# RevA.net
KiCad netlist of a schematic drawn in EAGLE
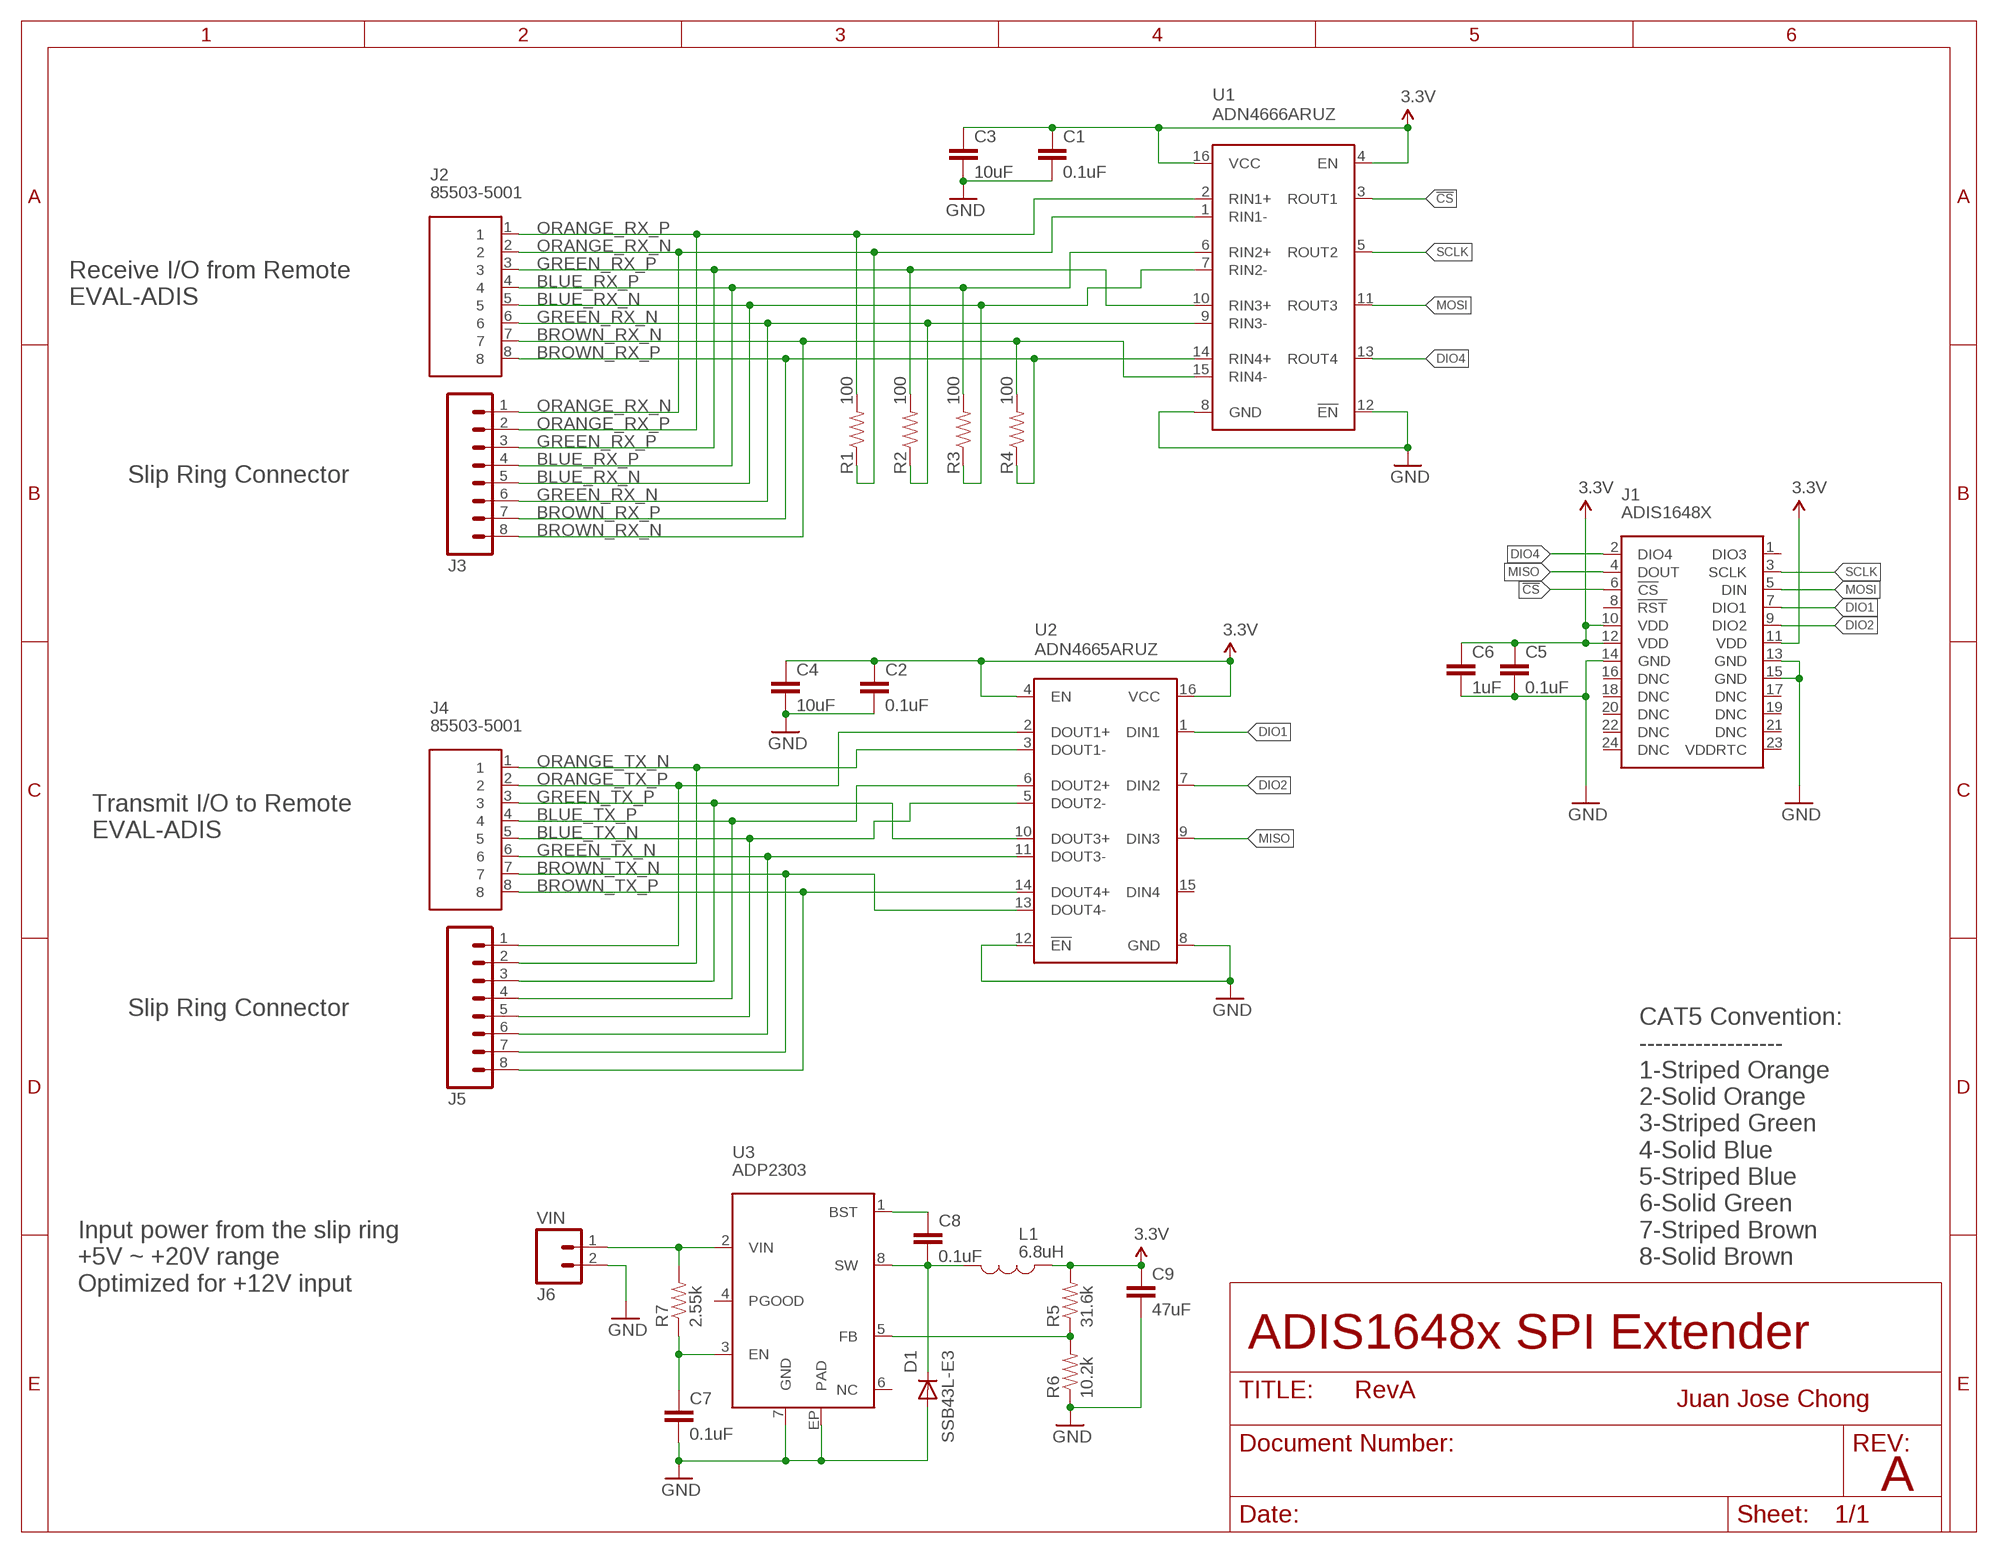
[diagram p0: schematic, sheet 1]

(export (version "E")
  (design (tool "Eeschema 10.0.6"))
  (components
    (comp (ref "C1")
      (value "0.1uF")
      (footprint "eagle-import:0603-CAP")
      (fields (field (name "PARTNO") "CL10B104KB8NNNC"))
      (libsource (lib "eagle-import") (part "CAP0603-CAP"))
    )
    (comp (ref "C2")
      (value "0.1uF")
      (footprint "eagle-import:0603-CAP")
      (fields (field (name "PARTNO") "CL10B104KB8NNNC"))
      (libsource (lib "eagle-import") (part "CAP0603-CAP"))
    )
    (comp (ref "C3")
      (value "10uF")
      (footprint "eagle-import:1206")
      (fields (field (name "PARTNO") "F931C106MAA"))
      (libsource (lib "eagle-import") (part "CAP1206"))
    )
    (comp (ref "C4")
      (value "10uF")
      (footprint "eagle-import:1206")
      (fields (field (name "PARTNO") "F931C106MAA"))
      (libsource (lib "eagle-import") (part "CAP1206"))
    )
    (comp (ref "C5")
      (value "0.1uF")
      (footprint "eagle-import:0603-CAP")
      (fields (field (name "PARTNO") "CL10B104KB8NNNC"))
      (libsource (lib "eagle-import") (part "CAP0603-CAP"))
    )
    (comp (ref "C6")
      (value "1uF")
      (footprint "eagle-import:0603-CAP")
      (fields (field (name "PARTNO") "GRM188R61C105KA93D"))
      (libsource (lib "eagle-import") (part "CAP0603-CAP"))
    )
    (comp (ref "C7")
      (value "0.1uF")
      (footprint "eagle-import:0603-CAP")
      (fields (field (name "PARTNO") "CL10B104KB8NNNC"))
      (libsource (lib "eagle-import") (part "CAP0603-CAP"))
    )
    (comp (ref "C8")
      (value "0.1uF")
      (footprint "eagle-import:0603-CAP")
      (fields (field (name "PARTNO") "CL10B104KB8NNNC"))
      (libsource (lib "eagle-import") (part "CAP0603-CAP"))
    )
    (comp (ref "C9")
      (value "47uF")
      (footprint "eagle-import:1206")
      (fields (field (name "PARTNO") "TLJA476M010R0600"))
      (libsource (lib "eagle-import") (part "CAP1206"))
    )
    (comp (ref "D1")
      (value "SSB43L-E3")
      (footprint "eagle-import:DO214AA")
      (fields (field (name "PARTNO") "SSB43L-E3/52T"))
      (libsource (lib "eagle-import") (part "DIODE-DO214AA"))
    )
    (comp (ref "J1")
      (value "ADIS1648X")
      (footprint "eagle-import:ADIS1648X")
      (libsource (lib "eagle-import") (part "ADIS1648X"))
    )
    (comp (ref "J2")
      (value "85503-5001")
      (footprint "eagle-import:85503-5001")
      (fields (field (name "PARTNO") "855035001"))
      (libsource (lib "eagle-import") (part "85503-5001"))
    )
    (comp (ref "J3")
      (value "M08LOCK")
      (footprint "eagle-import:1X08_LOCK")
      (libsource (lib "eagle-import") (part "M08LOCK"))
    )
    (comp (ref "J4")
      (value "85503-5001")
      (footprint "eagle-import:85503-5001")
      (fields (field (name "PARTNO") "855035001"))
      (libsource (lib "eagle-import") (part "85503-5001"))
    )
    (comp (ref "J5")
      (value "M08LOCK")
      (footprint "eagle-import:1X08_LOCK")
      (libsource (lib "eagle-import") (part "M08LOCK"))
    )
    (comp (ref "J6")
      (value "VIN")
      (footprint "eagle-import:SCREWTERMINAL-3.5MM-2")
      (libsource (lib "eagle-import") (part "M023.5MM"))
    )
    (comp (ref "L1")
      (value "6.8uH")
      (footprint "eagle-import:VLF10040")
      (fields (field (name "PARTNO") "VLF10040T-6R8N4R5"))
      (libsource (lib "eagle-import") (part "INDUCTOR"))
    )
    (comp (ref "R1")
      (value "100")
      (footprint "eagle-import:0603-RES")
      (fields (field (name "PARTNO") "ERJ-3EKF1000V"))
      (libsource (lib "eagle-import") (part "RESISTOR0603-RES"))
    )
    (comp (ref "R2")
      (value "100")
      (footprint "eagle-import:0603-RES")
      (fields (field (name "PARTNO") "ERJ-3EKF1000V"))
      (libsource (lib "eagle-import") (part "RESISTOR0603-RES"))
    )
    (comp (ref "R3")
      (value "100")
      (footprint "eagle-import:0603-RES")
      (fields (field (name "PARTNO") "ERJ-3EKF1000V"))
      (libsource (lib "eagle-import") (part "RESISTOR0603-RES"))
    )
    (comp (ref "R4")
      (value "100")
      (footprint "eagle-import:0603-RES")
      (fields (field (name "PARTNO") "ERJ-3EKF1000V"))
      (libsource (lib "eagle-import") (part "RESISTOR0603-RES"))
    )
    (comp (ref "R5")
      (value "31.6k")
      (footprint "eagle-import:0603-RES")
      (fields (field (name "PARTNO") "ERJ-3EKF3162V"))
      (libsource (lib "eagle-import") (part "RESISTOR0603-RES"))
    )
    (comp (ref "R6")
      (value "10.2k")
      (footprint "eagle-import:0603-RES")
      (fields (field (name "PARTNO") "ERJ-3EKF1022V"))
      (libsource (lib "eagle-import") (part "RESISTOR0603-RES"))
    )
    (comp (ref "R7")
      (value "2.55k")
      (footprint "eagle-import:0603-RES")
      (libsource (lib "eagle-import") (part "RESISTOR0603-RES"))
    )
    (comp (ref "U1")
      (value "ADN4666ARUZ")
      (footprint "eagle-import:TSSOP-16")
      (libsource (lib "eagle-import") (part "ADN4666ARUZ"))
    )
    (comp (ref "U2")
      (value "ADN4665ARUZ")
      (footprint "eagle-import:TSSOP-16")
      (libsource (lib "eagle-import") (part "ADN4665ARUZ"))
    )
    (comp (ref "U3")
      (value "ADP2303")
      (footprint "eagle-import:SOIC-8-PAD")
      (fields (field (name "PARTNO") "ADP2303ARDZ"))
      (libsource (lib "eagle-import") (part "ADP2303"))
    )
  )
  (nets
    (net (code "1") (name "/BLUE_RX_N") (class "Default")
      (node (ref "J2") (pin "5") (pinfunction "5_5") (pintype "bidirectional"))
      (node (ref "J3") (pin "5") (pinfunction "5_5") (pintype "passive"))
      (node (ref "R3") (pin "1") (pinfunction "1_1") (pintype "passive"))
      (node (ref "U1") (pin "7") (pinfunction "RIN2-_7") (pintype "bidirectional"))
    )
    (net (code "2") (name "/BLUE_RX_P") (class "Default")
      (node (ref "J2") (pin "4") (pinfunction "4_4") (pintype "bidirectional"))
      (node (ref "J3") (pin "4") (pinfunction "4_4") (pintype "passive"))
      (node (ref "R3") (pin "2") (pinfunction "2_2") (pintype "passive"))
      (node (ref "U1") (pin "6") (pinfunction "RIN2+_6") (pintype "bidirectional"))
    )
    (net (code "3") (name "/BLUE_TX_N") (class "Default")
      (node (ref "J4") (pin "5") (pinfunction "5_5") (pintype "bidirectional"))
      (node (ref "J5") (pin "5") (pinfunction "5_5") (pintype "passive"))
      (node (ref "U2") (pin "5") (pinfunction "DOUT2-_5") (pintype "bidirectional"))
    )
    (net (code "4") (name "/BLUE_TX_P") (class "Default")
      (node (ref "J4") (pin "4") (pinfunction "4_4") (pintype "bidirectional"))
      (node (ref "J5") (pin "4") (pinfunction "4_4") (pintype "passive"))
      (node (ref "U2") (pin "6") (pinfunction "DOUT2+_6") (pintype "bidirectional"))
    )
    (net (code "5") (name "/BROWN_RX_N") (class "Default")
      (node (ref "J2") (pin "7") (pinfunction "7_7") (pintype "bidirectional"))
      (node (ref "J3") (pin "8") (pinfunction "8_8") (pintype "passive"))
      (node (ref "R4") (pin "2") (pinfunction "2_2") (pintype "passive"))
      (node (ref "U1") (pin "15") (pinfunction "RIN4-_15") (pintype "bidirectional"))
    )
    (net (code "6") (name "/BROWN_RX_P") (class "Default")
      (node (ref "J2") (pin "8") (pinfunction "8_8") (pintype "bidirectional"))
      (node (ref "J3") (pin "7") (pinfunction "7_7") (pintype "passive"))
      (node (ref "R4") (pin "1") (pinfunction "1_1") (pintype "passive"))
      (node (ref "U1") (pin "14") (pinfunction "RIN4+_14") (pintype "bidirectional"))
    )
    (net (code "7") (name "/BROWN_TX_N") (class "Default")
      (node (ref "J4") (pin "7") (pinfunction "7_7") (pintype "bidirectional"))
      (node (ref "J5") (pin "7") (pinfunction "7_7") (pintype "passive"))
      (node (ref "U2") (pin "13") (pinfunction "DOUT4-_13") (pintype "bidirectional"))
    )
    (net (code "8") (name "/BROWN_TX_P") (class "Default")
      (node (ref "J4") (pin "8") (pinfunction "8_8") (pintype "bidirectional"))
      (node (ref "J5") (pin "8") (pinfunction "8_8") (pintype "passive"))
      (node (ref "U2") (pin "14") (pinfunction "DOUT4+_14") (pintype "bidirectional"))
    )
    (net (code "9") (name "/GREEN_RX_N") (class "Default")
      (node (ref "J2") (pin "6") (pinfunction "6_6") (pintype "bidirectional"))
      (node (ref "J3") (pin "6") (pinfunction "6_6") (pintype "passive"))
      (node (ref "R2") (pin "1") (pinfunction "1_1") (pintype "passive"))
      (node (ref "U1") (pin "9") (pinfunction "RIN3-_9") (pintype "bidirectional"))
    )
    (net (code "10") (name "/GREEN_RX_P") (class "Default")
      (node (ref "J2") (pin "3") (pinfunction "3_3") (pintype "bidirectional"))
      (node (ref "J3") (pin "3") (pinfunction "3_3") (pintype "passive"))
      (node (ref "R2") (pin "2") (pinfunction "2_2") (pintype "passive"))
      (node (ref "U1") (pin "10") (pinfunction "RIN3+_10") (pintype "bidirectional"))
    )
    (net (code "11") (name "/GREEN_TX_N") (class "Default")
      (node (ref "J4") (pin "6") (pinfunction "6_6") (pintype "bidirectional"))
      (node (ref "J5") (pin "6") (pinfunction "6_6") (pintype "passive"))
      (node (ref "U2") (pin "11") (pinfunction "DOUT3-_11") (pintype "bidirectional"))
    )
    (net (code "12") (name "/GREEN_TX_P") (class "Default")
      (node (ref "J4") (pin "3") (pinfunction "3_3") (pintype "bidirectional"))
      (node (ref "J5") (pin "3") (pinfunction "3_3") (pintype "passive"))
      (node (ref "U2") (pin "10") (pinfunction "DOUT3+_10") (pintype "bidirectional"))
    )
    (net (code "13") (name "/ORANGE_RX_N") (class "Default")
      (node (ref "J2") (pin "2") (pinfunction "2_2") (pintype "bidirectional"))
      (node (ref "J3") (pin "1") (pinfunction "1_1") (pintype "passive"))
      (node (ref "R1") (pin "1") (pinfunction "1_1") (pintype "passive"))
      (node (ref "U1") (pin "1") (pinfunction "RIN1-_1") (pintype "bidirectional"))
    )
    (net (code "14") (name "/ORANGE_RX_P") (class "Default")
      (node (ref "J2") (pin "1") (pinfunction "1_1") (pintype "bidirectional"))
      (node (ref "J3") (pin "2") (pinfunction "2_2") (pintype "passive"))
      (node (ref "R1") (pin "2") (pinfunction "2_2") (pintype "passive"))
      (node (ref "U1") (pin "2") (pinfunction "RIN1+_2") (pintype "bidirectional"))
    )
    (net (code "15") (name "/ORANGE_TX_N") (class "Default")
      (node (ref "J4") (pin "1") (pinfunction "1_1") (pintype "bidirectional"))
      (node (ref "J5") (pin "2") (pinfunction "2_2") (pintype "passive"))
      (node (ref "U2") (pin "3") (pinfunction "DOUT1-_3") (pintype "bidirectional"))
    )
    (net (code "16") (name "/ORANGE_TX_P") (class "Default")
      (node (ref "J4") (pin "2") (pinfunction "2_2") (pintype "bidirectional"))
      (node (ref "J5") (pin "1") (pinfunction "1_1") (pintype "passive"))
      (node (ref "U2") (pin "2") (pinfunction "DOUT1+_2") (pintype "bidirectional"))
    )
    (net (code "17") (name "/~{CS}") (class "Default")
      (node (ref "J1") (pin "6") (pinfunction "~{CS}_6") (pintype "bidirectional"))
      (node (ref "U1") (pin "3") (pinfunction "ROUT1_3") (pintype "bidirectional"))
    )
    (net (code "18") (name "3.3V") (class "Default")
      (node (ref "C1") (pin "1") (pinfunction "1_1") (pintype "passive"))
      (node (ref "C2") (pin "1") (pinfunction "1_1") (pintype "passive"))
      (node (ref "C3") (pin "1") (pinfunction "1_1") (pintype "passive"))
      (node (ref "C4") (pin "1") (pinfunction "1_1") (pintype "passive"))
      (node (ref "C5") (pin "1") (pinfunction "1_1") (pintype "passive"))
      (node (ref "C6") (pin "1") (pinfunction "1_1") (pintype "passive"))
      (node (ref "C9") (pin "1") (pinfunction "1_1") (pintype "passive"))
      (node (ref "J1") (pin "10") (pinfunction "VDD_10") (pintype "bidirectional"))
      (node (ref "J1") (pin "11") (pinfunction "VDD_11") (pintype "bidirectional"))
      (node (ref "J1") (pin "12") (pinfunction "VDD_12") (pintype "bidirectional"))
      (node (ref "L1") (pin "P$1") (pinfunction "1_P$1") (pintype "passive"))
      (node (ref "R5") (pin "2") (pinfunction "2_2") (pintype "passive"))
      (node (ref "U1") (pin "16") (pinfunction "VCC_16") (pintype "bidirectional"))
      (node (ref "U1") (pin "4") (pinfunction "EN_4") (pintype "bidirectional"))
      (node (ref "U2") (pin "16") (pinfunction "VCC_16") (pintype "bidirectional"))
      (node (ref "U2") (pin "4") (pinfunction "EN_4") (pintype "bidirectional"))
    )
    (net (code "19") (name "DIO1") (class "Default")
      (node (ref "J1") (pin "7") (pinfunction "DIO1_7") (pintype "bidirectional"))
      (node (ref "U2") (pin "1") (pinfunction "DIN1_1") (pintype "bidirectional"))
    )
    (net (code "20") (name "DIO2") (class "Default")
      (node (ref "J1") (pin "9") (pinfunction "DIO2_9") (pintype "bidirectional"))
      (node (ref "U2") (pin "7") (pinfunction "DIN2_7") (pintype "bidirectional"))
    )
    (net (code "21") (name "DIO4") (class "Default")
      (node (ref "J1") (pin "2") (pinfunction "DIO4_2") (pintype "bidirectional"))
      (node (ref "U1") (pin "13") (pinfunction "ROUT4_13") (pintype "bidirectional"))
    )
    (net (code "22") (name "GND") (class "Default")
      (node (ref "C1") (pin "2") (pinfunction "2_2") (pintype "passive"))
      (node (ref "C2") (pin "2") (pinfunction "2_2") (pintype "passive"))
      (node (ref "C3") (pin "2") (pinfunction "2_2") (pintype "passive"))
      (node (ref "C4") (pin "2") (pinfunction "2_2") (pintype "passive"))
      (node (ref "C5") (pin "2") (pinfunction "2_2") (pintype "passive"))
      (node (ref "C6") (pin "2") (pinfunction "2_2") (pintype "passive"))
      (node (ref "C7") (pin "2") (pinfunction "2_2") (pintype "passive"))
      (node (ref "C9") (pin "2") (pinfunction "2_2") (pintype "passive"))
      (node (ref "D1") (pin "A") (pinfunction "A_A") (pintype "passive"))
      (node (ref "J1") (pin "13") (pinfunction "GND_13") (pintype "bidirectional"))
      (node (ref "J1") (pin "14") (pinfunction "GND_14") (pintype "bidirectional"))
      (node (ref "J1") (pin "15") (pinfunction "GND_15") (pintype "bidirectional"))
      (node (ref "J6") (pin "2") (pinfunction "2_2") (pintype "passive"))
      (node (ref "R6") (pin "1") (pinfunction "1_1") (pintype "passive"))
      (node (ref "U1") (pin "12") (pinfunction "~{EN}_12") (pintype "bidirectional"))
      (node (ref "U1") (pin "8") (pinfunction "GND_8") (pintype "bidirectional"))
      (node (ref "U2") (pin "12") (pinfunction "~{EN}_12") (pintype "bidirectional"))
      (node (ref "U2") (pin "8") (pinfunction "GND_8") (pintype "bidirectional"))
      (node (ref "U3") (pin "7") (pinfunction "GND_7") (pintype "bidirectional"))
      (node (ref "U3") (pin "EP") (pinfunction "PAD_EP") (pintype "bidirectional"))
    )
    (net (code "23") (name "MISO") (class "Default")
      (node (ref "J1") (pin "4") (pinfunction "DOUT_4") (pintype "bidirectional"))
      (node (ref "U2") (pin "9") (pinfunction "DIN3_9") (pintype "bidirectional"))
    )
    (net (code "24") (name "MOSI") (class "Default")
      (node (ref "J1") (pin "5") (pinfunction "DIN_5") (pintype "bidirectional"))
      (node (ref "U1") (pin "11") (pinfunction "ROUT3_11") (pintype "bidirectional"))
    )
    (net (code "25") (name "Net-(L1-2)") (class "Default")
      (node (ref "C8") (pin "2") (pinfunction "2_2") (pintype "passive"))
      (node (ref "D1") (pin "C") (pinfunction "C_C") (pintype "passive"))
      (node (ref "L1") (pin "P$2") (pinfunction "2_P$2") (pintype "passive"))
      (node (ref "U3") (pin "8") (pinfunction "SW_8") (pintype "bidirectional"))
    )
    (net (code "26") (name "Net-(U3-BST)") (class "Default")
      (node (ref "C8") (pin "1") (pinfunction "1_1") (pintype "passive"))
      (node (ref "U3") (pin "1") (pinfunction "BST_1") (pintype "bidirectional"))
    )
    (net (code "27") (name "Net-(U3-EN)") (class "Default")
      (node (ref "C7") (pin "1") (pinfunction "1_1") (pintype "passive"))
      (node (ref "R7") (pin "1") (pinfunction "1_1") (pintype "passive"))
      (node (ref "U3") (pin "3") (pinfunction "EN_3") (pintype "bidirectional"))
    )
    (net (code "28") (name "Net-(U3-FB)") (class "Default")
      (node (ref "R5") (pin "1") (pinfunction "1_1") (pintype "passive"))
      (node (ref "R6") (pin "2") (pinfunction "2_2") (pintype "passive"))
      (node (ref "U3") (pin "5") (pinfunction "FB_5") (pintype "bidirectional"))
    )
    (net (code "29") (name "Net-(U3-VIN)") (class "Default")
      (node (ref "J6") (pin "1") (pinfunction "1_1") (pintype "passive"))
      (node (ref "R7") (pin "2") (pinfunction "2_2") (pintype "passive"))
      (node (ref "U3") (pin "2") (pinfunction "VIN_2") (pintype "bidirectional"))
    )
    (net (code "30") (name "SCLK") (class "Default")
      (node (ref "J1") (pin "3") (pinfunction "SCLK_3") (pintype "bidirectional"))
      (node (ref "U1") (pin "5") (pinfunction "ROUT2_5") (pintype "bidirectional"))
    )
    (net (code "31") (name "unconnected-(J1-DIO3-Pad1)") (class "Default")
      (node (ref "J1") (pin "1") (pinfunction "DIO3_1") (pintype "bidirectional"))
    )
    (net (code "32") (name "unconnected-(J1-DNC-Pad16)") (class "Default")
      (node (ref "J1") (pin "16") (pinfunction "DNC_16") (pintype "bidirectional"))
    )
    (net (code "33") (name "unconnected-(J1-DNC-Pad17)") (class "Default")
      (node (ref "J1") (pin "17") (pinfunction "DNC_17") (pintype "bidirectional"))
    )
    (net (code "34") (name "unconnected-(J1-DNC-Pad18)") (class "Default")
      (node (ref "J1") (pin "18") (pinfunction "DNC_18") (pintype "bidirectional"))
    )
    (net (code "35") (name "unconnected-(J1-DNC-Pad19)") (class "Default")
      (node (ref "J1") (pin "19") (pinfunction "DNC_19") (pintype "bidirectional"))
    )
    (net (code "36") (name "unconnected-(J1-DNC-Pad20)") (class "Default")
      (node (ref "J1") (pin "20") (pinfunction "DNC_20") (pintype "bidirectional"))
    )
    (net (code "37") (name "unconnected-(J1-DNC-Pad21)") (class "Default")
      (node (ref "J1") (pin "21") (pinfunction "DNC_21") (pintype "bidirectional"))
    )
    (net (code "38") (name "unconnected-(J1-DNC-Pad22)") (class "Default")
      (node (ref "J1") (pin "22") (pinfunction "DNC_22") (pintype "bidirectional"))
    )
    (net (code "39") (name "unconnected-(J1-DNC-Pad24)") (class "Default")
      (node (ref "J1") (pin "24") (pinfunction "DNC_24") (pintype "bidirectional"))
    )
    (net (code "40") (name "unconnected-(J1-VDDRTC-Pad23)") (class "Default")
      (node (ref "J1") (pin "23") (pinfunction "VDDRTC_23") (pintype "bidirectional"))
    )
    (net (code "41") (name "unconnected-(J1-~{RST}-Pad8)") (class "Default")
      (node (ref "J1") (pin "8") (pinfunction "~{RST}_8") (pintype "bidirectional"))
    )
    (net (code "42") (name "unconnected-(U2-DIN4-Pad15)") (class "Default")
      (node (ref "U2") (pin "15") (pinfunction "DIN4_15") (pintype "bidirectional"))
    )
    (net (code "43") (name "unconnected-(U3-NC-Pad6)") (class "Default")
      (node (ref "U3") (pin "6") (pinfunction "NC_6") (pintype "bidirectional"))
    )
    (net (code "44") (name "unconnected-(U3-PGOOD-Pad4)") (class "Default")
      (node (ref "U3") (pin "4") (pinfunction "PGOOD_4") (pintype "bidirectional"))
    )
  )
)
